# design_EasyDEA.net
KiCad netlist of a schematic drawn in EasyEDA
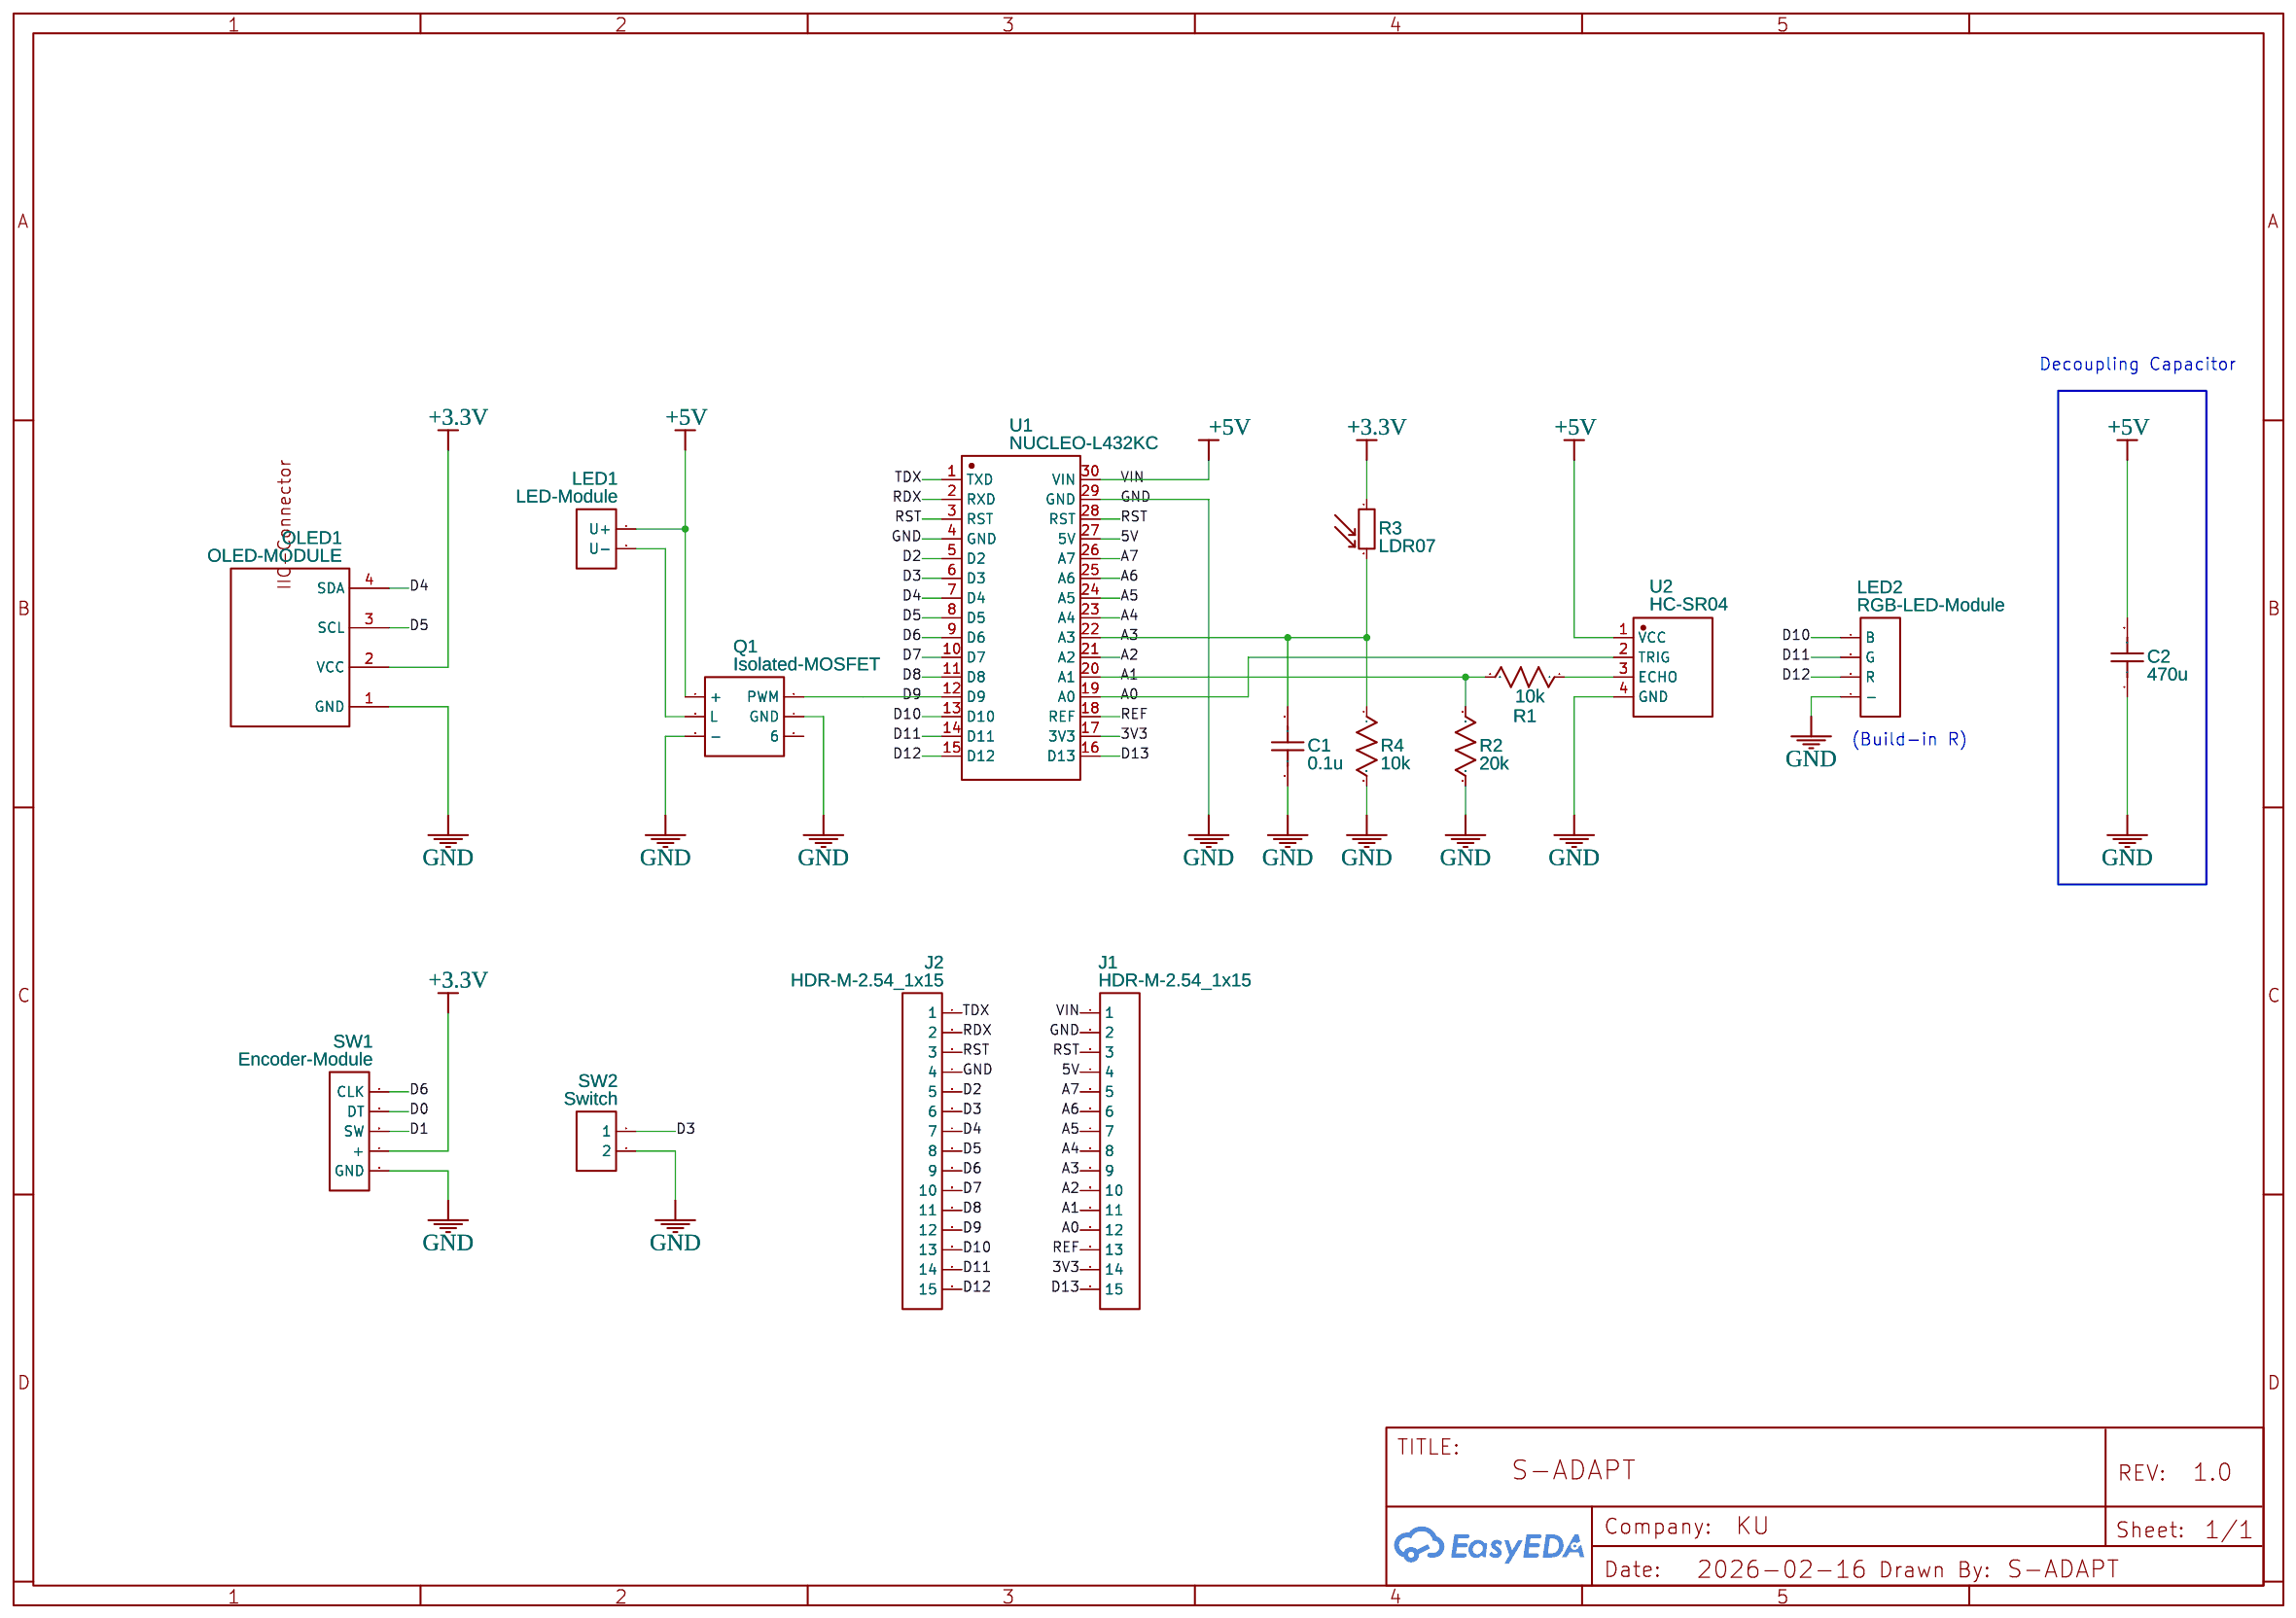
[diagram p0: schematic sheet]

(export (version "E")
  (design (tool "Eeschema 10.0.6"))
  (components
    (comp (ref "C1") (value "0.1u") (libsource (lib "") (part "C_0603_US")))
    (comp (ref "C2") (value "470u") (libsource (lib "") (part "C_0603_US")))
    (comp (ref "J1") (value "HDR-M-2.54_1x15") (libsource (lib "") (part "HDR-M-2.54_1x15_1")))
    (comp (ref "J2") (value "HDR-M-2.54_1x15") (libsource (lib "") (part "HDR-M-2.54_1x15")))
    (comp (ref "LED1") (value "LED-Module") (libsource (lib "") (part "HDR-M-2.54_1x2_1")))
    (comp (ref "LED2") (value "RGB-LED-Module") (libsource (lib "") (part "HDR-F-2.54_1x4")))
    (comp (ref "OLED1")
      (value "OLED-MODULE")
      (fields (field (name "Manufacturer Part") "0.96OLED_4P_MODULE_JX"))
      (libsource (lib "") (part "0.96OLED_4P_MODULE_JX"))
    )
    (comp (ref "Q1")
      (value "Isolated-MOSFET")
      (fields (field (name "Manufacturer Part") "2X3 2.54mm IDC Box") (field (name "Manufacturer") "BOOMELE"))
      (libsource (lib "") (part "HDR-IDC-2.54-2X3P"))
    )
    (comp (ref "R1") (value "10k") (libsource (lib "") (part "R_0603_US_1")))
    (comp (ref "R2") (value "20k") (libsource (lib "") (part "R_0603_US")))
    (comp (ref "R3") (value "LDR07") (libsource (lib "") (part "LDR07")))
    (comp (ref "R4") (value "10k") (libsource (lib "") (part "R_0603_US_2")))
    (comp (ref "SW1") (value "Encoder-Module") (libsource (lib "") (part "HDR-F-2.54_1x5")))
    (comp (ref "SW2") (value "Switch") (libsource (lib "") (part "HDR-M-2.54_1x2")))
    (comp (ref "U1")
      (value "NUCLEO-L432KC")
      (fields (field (name "Manufacturer") "ST(意法半导体)"))
      (libsource (lib "") (part "NUCLEO-L432KC"))
    )
    (comp (ref "U2")
      (value "HC-SR04")
      (fields (field (name "Manufacturer") "Universal Microelectronics"))
      (libsource (lib "") (part "HC-SR04"))
    )
  )
  (nets
    (net (code "1") (name "+3.3V") (class "Default")
      (node (ref "OLED1") (pin "2") (pinfunction "VCC_2") (pintype "unspecified"))
      (node (ref "R3") (pin "1") (pintype "unspecified"))
      (node (ref "SW1") (pin "4") (pinfunction "+_4") (pintype "unspecified"))
    )
    (net (code "2") (name "+5V") (class "Default")
      (node (ref "C2") (pin "2") (pinfunction "2_2") (pintype "unspecified"))
      (node (ref "J1") (pin "1") (pinfunction "1_1") (pintype "unspecified"))
      (node (ref "LED1") (pin "1") (pinfunction "U+_1") (pintype "unspecified"))
      (node (ref "Q1") (pin "1") (pinfunction "+_1") (pintype "unspecified"))
      (node (ref "U1") (pin "30") (pinfunction "VIN_30") (pintype "unspecified"))
      (node (ref "U2") (pin "1") (pinfunction "VCC_1") (pintype "unspecified"))
    )
    (net (code "3") (name "/3V3") (class "Default")
      (node (ref "J1") (pin "14") (pinfunction "14_14") (pintype "unspecified"))
      (node (ref "U1") (pin "17") (pinfunction "3V3_17") (pintype "unspecified"))
    )
    (net (code "4") (name "/5V") (class "Default")
      (node (ref "J1") (pin "4") (pinfunction "4_4") (pintype "unspecified"))
      (node (ref "U1") (pin "27") (pinfunction "5V_27") (pintype "unspecified"))
    )
    (net (code "5") (name "/A0") (class "Default")
      (node (ref "J1") (pin "12") (pinfunction "12_12") (pintype "unspecified"))
      (node (ref "U1") (pin "19") (pinfunction "A0_19") (pintype "unspecified"))
      (node (ref "U2") (pin "2") (pinfunction "TRIG_2") (pintype "unspecified"))
    )
    (net (code "6") (name "/A1") (class "Default")
      (node (ref "J1") (pin "11") (pinfunction "11_11") (pintype "unspecified"))
      (node (ref "R1") (pin "2") (pinfunction "2_2") (pintype "unspecified"))
      (node (ref "R2") (pin "2") (pinfunction "2_2") (pintype "unspecified"))
      (node (ref "U1") (pin "20") (pinfunction "A1_20") (pintype "unspecified"))
    )
    (net (code "7") (name "/A2") (class "Default")
      (node (ref "J1") (pin "10") (pinfunction "10_10") (pintype "unspecified"))
      (node (ref "U1") (pin "21") (pinfunction "A2_21") (pintype "unspecified"))
    )
    (net (code "8") (name "/A3") (class "Default")
      (node (ref "C1") (pin "2") (pinfunction "2_2") (pintype "unspecified"))
      (node (ref "J1") (pin "9") (pinfunction "9_9") (pintype "unspecified"))
      (node (ref "R3") (pin "2") (pintype "unspecified"))
      (node (ref "R4") (pin "1") (pinfunction "1_1") (pintype "unspecified"))
      (node (ref "U1") (pin "22") (pinfunction "A3_22") (pintype "unspecified"))
    )
    (net (code "9") (name "/A4") (class "Default")
      (node (ref "J1") (pin "8") (pinfunction "8_8") (pintype "unspecified"))
      (node (ref "U1") (pin "23") (pinfunction "A4_23") (pintype "unspecified"))
    )
    (net (code "10") (name "/A5") (class "Default")
      (node (ref "J1") (pin "7") (pinfunction "7_7") (pintype "unspecified"))
      (node (ref "U1") (pin "24") (pinfunction "A5_24") (pintype "unspecified"))
    )
    (net (code "11") (name "/A6") (class "Default")
      (node (ref "J1") (pin "6") (pinfunction "6_6") (pintype "unspecified"))
      (node (ref "U1") (pin "25") (pinfunction "A6_25") (pintype "unspecified"))
    )
    (net (code "12") (name "/A7") (class "Default")
      (node (ref "J1") (pin "5") (pinfunction "5_5") (pintype "unspecified"))
      (node (ref "U1") (pin "26") (pinfunction "A7_26") (pintype "unspecified"))
    )
    (net (code "13") (name "/D0") (class "Default")
      (node (ref "SW1") (pin "2") (pinfunction "DT_2") (pintype "unspecified"))
    )
    (net (code "14") (name "/D1") (class "Default")
      (node (ref "SW1") (pin "3") (pinfunction "SW_3") (pintype "unspecified"))
    )
    (net (code "15") (name "/D2") (class "Default")
      (node (ref "J2") (pin "5") (pinfunction "5_5") (pintype "unspecified"))
      (node (ref "U1") (pin "5") (pinfunction "D2_5") (pintype "unspecified"))
    )
    (net (code "16") (name "/D3") (class "Default")
      (node (ref "J2") (pin "6") (pinfunction "6_6") (pintype "unspecified"))
      (node (ref "SW2") (pin "1") (pinfunction "1_1") (pintype "unspecified"))
      (node (ref "U1") (pin "6") (pinfunction "D3_6") (pintype "unspecified"))
    )
    (net (code "17") (name "/D4") (class "Default")
      (node (ref "J2") (pin "7") (pinfunction "7_7") (pintype "unspecified"))
      (node (ref "OLED1") (pin "4") (pinfunction "SDA_4") (pintype "unspecified"))
      (node (ref "U1") (pin "7") (pinfunction "D4_7") (pintype "unspecified"))
    )
    (net (code "18") (name "/D5") (class "Default")
      (node (ref "J2") (pin "8") (pinfunction "8_8") (pintype "unspecified"))
      (node (ref "OLED1") (pin "3") (pinfunction "SCL_3") (pintype "unspecified"))
      (node (ref "U1") (pin "8") (pinfunction "D5_8") (pintype "unspecified"))
    )
    (net (code "19") (name "/D6") (class "Default")
      (node (ref "J2") (pin "9") (pinfunction "9_9") (pintype "unspecified"))
      (node (ref "SW1") (pin "1") (pinfunction "CLK_1") (pintype "unspecified"))
      (node (ref "U1") (pin "9") (pinfunction "D6_9") (pintype "unspecified"))
    )
    (net (code "20") (name "/D7") (class "Default")
      (node (ref "J2") (pin "10") (pinfunction "10_10") (pintype "unspecified"))
      (node (ref "U1") (pin "10") (pinfunction "D7_10") (pintype "unspecified"))
    )
    (net (code "21") (name "/D8") (class "Default")
      (node (ref "J2") (pin "11") (pinfunction "11_11") (pintype "unspecified"))
      (node (ref "U1") (pin "11") (pinfunction "D8_11") (pintype "unspecified"))
    )
    (net (code "22") (name "/D9") (class "Default")
      (node (ref "J2") (pin "12") (pinfunction "12_12") (pintype "unspecified"))
      (node (ref "Q1") (pin "2") (pinfunction "PWM_2") (pintype "unspecified"))
      (node (ref "U1") (pin "12") (pinfunction "D9_12") (pintype "unspecified"))
    )
    (net (code "23") (name "/D10") (class "Default")
      (node (ref "J2") (pin "13") (pinfunction "13_13") (pintype "unspecified"))
      (node (ref "LED2") (pin "1") (pinfunction "B_1") (pintype "unspecified"))
      (node (ref "U1") (pin "13") (pinfunction "D10_13") (pintype "unspecified"))
    )
    (net (code "24") (name "/D11") (class "Default")
      (node (ref "J2") (pin "14") (pinfunction "14_14") (pintype "unspecified"))
      (node (ref "LED2") (pin "2") (pinfunction "G_2") (pintype "unspecified"))
      (node (ref "U1") (pin "14") (pinfunction "D11_14") (pintype "unspecified"))
    )
    (net (code "25") (name "/D12") (class "Default")
      (node (ref "J2") (pin "15") (pinfunction "15_15") (pintype "unspecified"))
      (node (ref "LED2") (pin "3") (pinfunction "R_3") (pintype "unspecified"))
      (node (ref "U1") (pin "15") (pinfunction "D12_15") (pintype "unspecified"))
    )
    (net (code "26") (name "/D13") (class "Default")
      (node (ref "J1") (pin "15") (pinfunction "15_15") (pintype "unspecified"))
      (node (ref "U1") (pin "16") (pinfunction "D13_16") (pintype "unspecified"))
    )
    (net (code "27") (name "/RDX") (class "Default")
      (node (ref "J2") (pin "2") (pinfunction "2_2") (pintype "unspecified"))
      (node (ref "U1") (pin "2") (pinfunction "RXD_2") (pintype "unspecified"))
    )
    (net (code "28") (name "/REF") (class "Default")
      (node (ref "J1") (pin "13") (pinfunction "13_13") (pintype "unspecified"))
      (node (ref "U1") (pin "18") (pinfunction "REF_18") (pintype "unspecified"))
    )
    (net (code "29") (name "/RST") (class "Default")
      (node (ref "J1") (pin "3") (pinfunction "3_3") (pintype "unspecified"))
      (node (ref "J2") (pin "3") (pinfunction "3_3") (pintype "unspecified"))
      (node (ref "U1") (pin "28") (pinfunction "RST_28") (pintype "unspecified"))
      (node (ref "U1") (pin "3") (pinfunction "RST_3") (pintype "unspecified"))
    )
    (net (code "30") (name "/TDX") (class "Default")
      (node (ref "J2") (pin "1") (pinfunction "1_1") (pintype "unspecified"))
      (node (ref "U1") (pin "1") (pinfunction "TXD_1") (pintype "unspecified"))
    )
    (net (code "31") (name "GND") (class "Default")
      (node (ref "C1") (pin "1") (pinfunction "1_1") (pintype "unspecified"))
      (node (ref "C2") (pin "1") (pinfunction "1_1") (pintype "unspecified"))
      (node (ref "J1") (pin "2") (pinfunction "2_2") (pintype "unspecified"))
      (node (ref "J2") (pin "4") (pinfunction "4_4") (pintype "unspecified"))
      (node (ref "LED2") (pin "4") (pinfunction "-_4") (pintype "unspecified"))
      (node (ref "OLED1") (pin "1") (pinfunction "GND_1") (pintype "unspecified"))
      (node (ref "Q1") (pin "4") (pinfunction "GND_4") (pintype "unspecified"))
      (node (ref "Q1") (pin "5") (pinfunction "-_5") (pintype "unspecified"))
      (node (ref "R2") (pin "1") (pinfunction "1_1") (pintype "unspecified"))
      (node (ref "R4") (pin "2") (pinfunction "2_2") (pintype "unspecified"))
      (node (ref "SW1") (pin "5") (pinfunction "GND_5") (pintype "unspecified"))
      (node (ref "SW2") (pin "2") (pinfunction "2_2") (pintype "unspecified"))
      (node (ref "U1") (pin "29") (pinfunction "GND_29") (pintype "unspecified"))
      (node (ref "U1") (pin "4") (pinfunction "GND_4") (pintype "unspecified"))
      (node (ref "U2") (pin "4") (pinfunction "GND_4") (pintype "unspecified"))
    )
    (net (code "32") (name "Net-(LED1-U-)") (class "Default")
      (node (ref "LED1") (pin "2") (pinfunction "U-_2") (pintype "unspecified"))
      (node (ref "Q1") (pin "3") (pinfunction "L_3") (pintype "unspecified"))
    )
    (net (code "33") (name "Net-(U2-ECHO)") (class "Default")
      (node (ref "R1") (pin "1") (pinfunction "1_1") (pintype "unspecified"))
      (node (ref "U2") (pin "3") (pinfunction "ECHO_3") (pintype "unspecified"))
    )
    (net (code "34") (name "unconnected-(Q1-Pad6)") (class "Default")
      (node (ref "Q1") (pin "6") (pinfunction "6_6") (pintype "unspecified"))
    )
  )
)
